# SQUID_Channel.net
KiCad netlist of a schematic drawn in Altium Designer
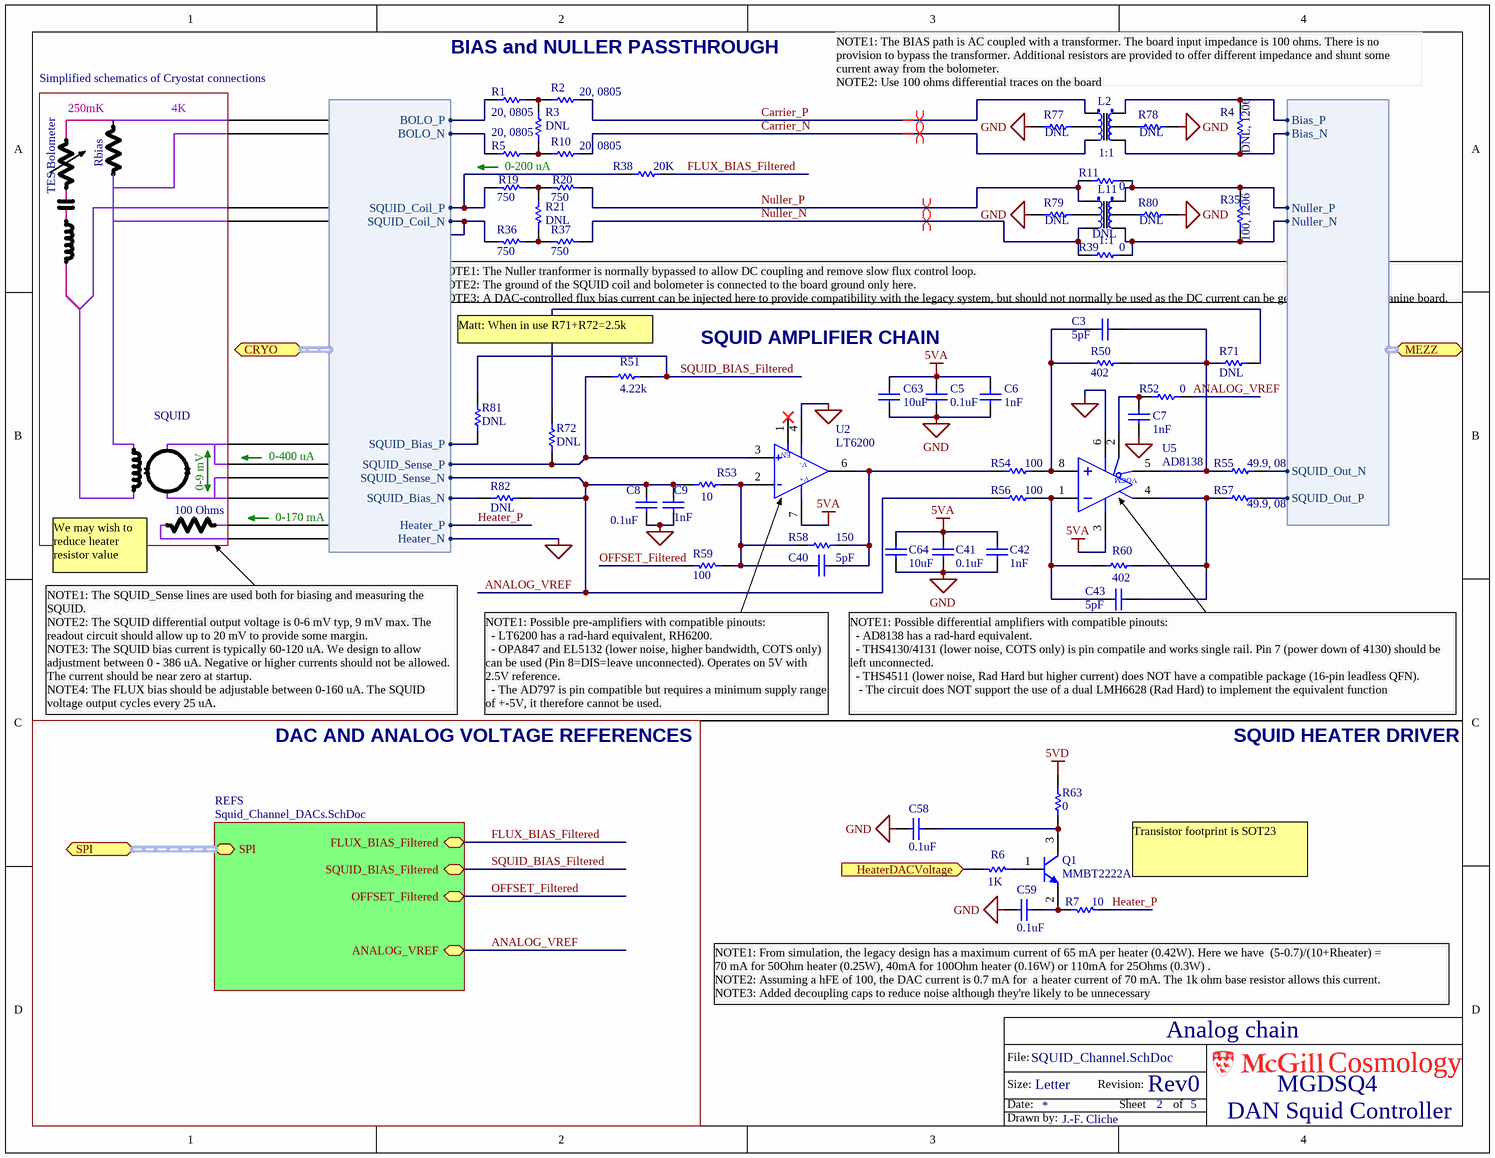
[diagram p0: SQUID_Channel.SchDoc]

(export (version "E")
  (design (tool "Eeschema 10.0.6"))
  (components
    (comp (ref "C3")
      (value "5pF")
      (footprint "0603")
      (description "Capacitor, Ceramic, 0603")
      (fields (field (name "MANUFACTURER") "Generic"))
      (libsource (lib "MiniSquidCtrl") (part "Cap0603"))
    )
    (comp (ref "C5")
      (value "0.1uF")
      (footprint "0603")
      (description "Capacitor, Ceramic, 0603")
      (fields (field (name "MANUFACTURER") "Generic"))
      (libsource (lib "MiniSquidCtrl") (part "Cap0603"))
    )
    (comp (ref "C6")
      (value "1nF")
      (footprint "0603")
      (description "Capacitor, Ceramic, 0603")
      (fields (field (name "MANUFACTURER") "Generic"))
      (libsource (lib "MiniSquidCtrl") (part "Cap0603"))
    )
    (comp (ref "C7")
      (value "1nF")
      (footprint "0603")
      (description "Capacitor, Ceramic, 0603")
      (fields (field (name "MANUFACTURER") "Generic"))
      (libsource (lib "MiniSquidCtrl") (part "Cap0603"))
    )
    (comp (ref "C8")
      (value "0.1uF")
      (footprint "0603")
      (description "Capacitor, Ceramic, 0603")
      (fields (field (name "MANUFACTURER") "Generic"))
      (libsource (lib "MiniSquidCtrl") (part "Cap0603"))
    )
    (comp (ref "C9")
      (value "1nF")
      (footprint "0603")
      (description "Capacitor, Ceramic, 0603")
      (fields (field (name "MANUFACTURER") "Generic"))
      (libsource (lib "MiniSquidCtrl") (part "Cap0603"))
    )
    (comp (ref "C40")
      (value "5pF")
      (footprint "0603")
      (description "Capacitor, Ceramic, 0603")
      (fields (field (name "MANUFACTURER") "Generic"))
      (libsource (lib "MiniSquidCtrl") (part "Cap0603"))
    )
    (comp (ref "C41")
      (value "0.1uF")
      (footprint "0603")
      (description "Capacitor, Ceramic, 0603")
      (fields (field (name "MANUFACTURER") "Generic"))
      (libsource (lib "MiniSquidCtrl") (part "Cap0603"))
    )
    (comp (ref "C42")
      (value "1nF")
      (footprint "0603")
      (description "Capacitor, Ceramic, 0603")
      (fields (field (name "MANUFACTURER") "Generic"))
      (libsource (lib "MiniSquidCtrl") (part "Cap0603"))
    )
    (comp (ref "C43")
      (value "5pF")
      (footprint "0603")
      (description "Capacitor, Ceramic, 0603")
      (fields (field (name "MANUFACTURER") "Generic"))
      (libsource (lib "MiniSquidCtrl") (part "Cap0603"))
    )
    (comp (ref "C58")
      (value "0.1uF")
      (footprint "0603")
      (description "Capacitor, Ceramic, 0603")
      (fields (field (name "MANUFACTURER") "Generic"))
      (libsource (lib "MiniSquidCtrl") (part "Cap0603"))
    )
    (comp (ref "C59")
      (value "0.1uF")
      (footprint "0603")
      (description "Capacitor, Ceramic, 0603")
      (fields (field (name "MANUFACTURER") "Generic"))
      (libsource (lib "MiniSquidCtrl") (part "Cap0603"))
    )
    (comp (ref "C63")
      (value "10uF")
      (footprint "CC3225-1210")
      (description "Capacitor, Ceramic, 1210")
      (fields (field (name "MANUFACTURER PART NUMBER") "1206YD106KAT2A") (field (name "VOLTAGE") "16V"))
      (libsource (lib "MiniSquidCtrl") (part "CAP 1210"))
    )
    (comp (ref "C64")
      (value "10uF")
      (footprint "CC3225-1210")
      (description "Capacitor, Ceramic, 1210")
      (fields (field (name "MANUFACTURER PART NUMBER") "1206YD106KAT2A") (field (name "VOLTAGE") "16V"))
      (libsource (lib "MiniSquidCtrl") (part "CAP 1210"))
    )
    (comp (ref "L2")
      (value "Transformer")
      (footprint "TTWB")
      (fields (field (name "MANUFACTURER") "Coilcraft"))
      (libsource (lib "MiniSquidCtrl") (part "Transformer"))
    )
    (comp (ref "L11")
      (value "DNL")
      (footprint "TTWB")
      (description "Transformer")
      (fields (field (name "MANUFACTURER") "Coilcraft"))
      (libsource (lib "MiniSquidCtrl") (part "Transformer"))
    )
    (comp (ref "Q1")
      (value "MMBT2222A")
      (footprint "SOT23")
      (description "TRANS NPN 40V 350MW SMD SOT23-3")
      (fields (field (name "MANUFACTURER") "Diodes Inc"))
      (libsource (lib "MiniSquidCtrl") (part "2N2222"))
    )
    (comp (ref "R1")
      (value "20, 0805")
      (footprint "0805")
      (description "RES 0805 SMD")
      (fields (field (name "MANUFACTURER") "Generic"))
      (libsource (lib "MiniSquidCtrl") (part "RES 0805"))
    )
    (comp (ref "R2")
      (value "20, 0805")
      (footprint "0805")
      (description "RES 0805 SMD")
      (fields (field (name "MANUFACTURER") "Generic"))
      (libsource (lib "MiniSquidCtrl") (part "RES 0805"))
    )
    (comp (ref "R3")
      (value "DNL")
      (footprint "0805")
      (description "RES 0805 SMD")
      (fields (field (name "MANUFACTURER") "Generic"))
      (libsource (lib "MiniSquidCtrl") (part "RES 0805"))
    )
    (comp (ref "R4")
      (value "DNL, 1206")
      (footprint "1206")
      (description "RES 100 OHM 1/4W 1206 SMD")
      (fields
        (field (name "MANUFACTURERS PART NUMBER") "DNL")
        (field (name "MANUFACTURER") "Rohm Semiconductor")
      )
      (libsource (lib "MiniSquidCtrl") (part "RES 1206"))
    )
    (comp (ref "R5")
      (value "20, 0805")
      (footprint "0805")
      (description "RES 0805 SMD")
      (fields (field (name "MANUFACTURER") "Generic"))
      (libsource (lib "MiniSquidCtrl") (part "RES 0805"))
    )
    (comp (ref "R6")
      (value "1K")
      (footprint "0603")
      (description "RES 0603")
      (fields (field (name "MANUFACTURER") "Generic") (field (name "Comment") "1k"))
      (libsource (lib "MiniSquidCtrl") (part "RES 0603"))
    )
    (comp (ref "R7")
      (value "10")
      (footprint "0603")
      (description "RES 0603")
      (fields (field (name "MANUFACTURER") "Generic"))
      (libsource (lib "MiniSquidCtrl") (part "RES 0603"))
    )
    (comp (ref "R10")
      (value "20, 0805")
      (footprint "0805")
      (description "RES 0805 SMD")
      (fields (field (name "MANUFACTURER") "Generic"))
      (libsource (lib "MiniSquidCtrl") (part "RES 0805"))
    )
    (comp (ref "R11")
      (value "0")
      (footprint "0603")
      (description "RES 0603")
      (fields (field (name "MANUFACTURER") "Generic"))
      (libsource (lib "MiniSquidCtrl") (part "Res0603"))
    )
    (comp (ref "R19")
      (value "750")
      (footprint "0603")
      (description "RES 0603")
      (fields (field (name "MANUFACTURER") "Generic"))
      (libsource (lib "MiniSquidCtrl") (part "Res0603"))
    )
    (comp (ref "R20")
      (value "750")
      (footprint "0603")
      (description "RES 0603")
      (fields (field (name "MANUFACTURER") "Generic"))
      (libsource (lib "MiniSquidCtrl") (part "Res0603"))
    )
    (comp (ref "R21")
      (value "DNL")
      (footprint "0603")
      (description "RES 0603")
      (fields (field (name "MANUFACTURER") "Generic"))
      (libsource (lib "MiniSquidCtrl") (part "Res0603"))
    )
    (comp (ref "R35")
      (value "100, 1206")
      (footprint "1206")
      (description "RES 100 OHM 1/4W 1206 SMD")
      (fields
        (field (name "MANUFACTURERS PART NUMBER") "ESR18EZPF1000")
        (field (name "MANUFACTURER") "Rohm Semiconductor")
      )
      (libsource (lib "MiniSquidCtrl") (part "RES 1206"))
    )
    (comp (ref "R36")
      (value "750")
      (footprint "0603")
      (description "RES 0603")
      (fields (field (name "MANUFACTURER") "Generic"))
      (libsource (lib "MiniSquidCtrl") (part "Res0603"))
    )
    (comp (ref "R37")
      (value "750")
      (footprint "0603")
      (description "RES 0603")
      (fields (field (name "MANUFACTURER") "Generic"))
      (libsource (lib "MiniSquidCtrl") (part "Res0603"))
    )
    (comp (ref "R38")
      (value "20K")
      (footprint "0603")
      (description "RES 0603")
      (fields (field (name "MANUFACTURER") "Generic") (field (name "Comment") "20k"))
      (libsource (lib "MiniSquidCtrl") (part "Res0603"))
    )
    (comp (ref "R39")
      (value "0")
      (footprint "0603")
      (description "RES 0603")
      (fields (field (name "MANUFACTURER") "Generic"))
      (libsource (lib "MiniSquidCtrl") (part "Res0603"))
    )
    (comp (ref "R48")
      (value "0")
      (footprint "0603")
      (description "RES 0603")
      (fields (field (name "MANUFACTURER") "Generic"))
      (libsource (lib "MiniSquidCtrl") (part "Res0603"))
    )
    (comp (ref "R50")
      (value "402")
      (footprint "0603")
      (description "RES 0603")
      (fields (field (name "MANUFACTURER") "Generic"))
      (libsource (lib "MiniSquidCtrl") (part "RES 0603"))
    )
    (comp (ref "R51")
      (value "4.22k")
      (footprint "0603")
      (description "RES 0603")
      (fields (field (name "MANUFACTURER") "Generic"))
      (libsource (lib "MiniSquidCtrl") (part "Res0603"))
    )
    (comp (ref "R52")
      (value "0")
      (footprint "0603")
      (description "RES 0603")
      (fields (field (name "MANUFACTURER") "Generic"))
      (libsource (lib "MiniSquidCtrl") (part "Res0603"))
    )
    (comp (ref "R53")
      (value "10")
      (footprint "0603")
      (description "RES 0603")
      (fields (field (name "MANUFACTURER") "Generic"))
      (libsource (lib "MiniSquidCtrl") (part "Res0603"))
    )
    (comp (ref "R54")
      (value "100")
      (footprint "0603")
      (description "RES 0603")
      (fields (field (name "MANUFACTURER") "Generic"))
      (libsource (lib "MiniSquidCtrl") (part "Res0603"))
    )
    (comp (ref "R55")
      (value "49.9, 0805")
      (footprint "0805")
      (description "RES 0805 SMD")
      (fields (field (name "MANUFACTURER") "Generic"))
      (libsource (lib "MiniSquidCtrl") (part "RES 0805"))
    )
    (comp (ref "R56")
      (value "100")
      (footprint "0603")
      (description "RES 0603")
      (fields (field (name "MANUFACTURER") "Generic"))
      (libsource (lib "MiniSquidCtrl") (part "Res0603"))
    )
    (comp (ref "R57")
      (value "49.9, 0805")
      (footprint "0805")
      (description "RES 0805 SMD")
      (fields (field (name "MANUFACTURER") "Generic"))
      (libsource (lib "MiniSquidCtrl") (part "RES 0805"))
    )
    (comp (ref "R58")
      (value "150")
      (footprint "0603")
      (description "RES 0603")
      (fields (field (name "MANUFACTURER") "Generic"))
      (libsource (lib "MiniSquidCtrl") (part "Res0603"))
    )
    (comp (ref "R59")
      (value "100")
      (footprint "0603")
      (description "RES 0603")
      (fields (field (name "MANUFACTURER") "Generic"))
      (libsource (lib "MiniSquidCtrl") (part "Res0603"))
    )
    (comp (ref "R60")
      (value "402")
      (footprint "0603")
      (description "RES 0603")
      (fields (field (name "MANUFACTURER") "Generic"))
      (libsource (lib "MiniSquidCtrl") (part "Res0603"))
    )
    (comp (ref "R63")
      (value "0")
      (footprint "0603")
      (description "RES 0603")
      (fields (field (name "MANUFACTURER") "Generic"))
      (libsource (lib "MiniSquidCtrl") (part "Res0603"))
    )
    (comp (ref "R71")
      (value "DNL")
      (footprint "0603")
      (description "RES 0603")
      (fields (field (name "MANUFACTURER") "Generic"))
      (libsource (lib "MiniSquidCtrl") (part "Res0603"))
    )
    (comp (ref "R72")
      (value "DNL")
      (footprint "0603")
      (description "RES 0603")
      (fields (field (name "MANUFACTURER") "Generic"))
      (libsource (lib "MiniSquidCtrl") (part "Res0603"))
    )
    (comp (ref "R77")
      (value "DNL")
      (footprint "0603")
      (description "RES 0603")
      (fields (field (name "MANUFACTURER") "Generic"))
      (libsource (lib "MiniSquidCtrl") (part "Res0603"))
    )
    (comp (ref "R78")
      (value "DNL")
      (footprint "0603")
      (description "RES 0603")
      (fields (field (name "MANUFACTURER") "Generic"))
      (libsource (lib "MiniSquidCtrl") (part "Res0603"))
    )
    (comp (ref "R79")
      (value "DNL")
      (footprint "0603")
      (description "RES 0603")
      (fields (field (name "MANUFACTURER") "Generic"))
      (libsource (lib "MiniSquidCtrl") (part "Res0603"))
    )
    (comp (ref "R80")
      (value "DNL")
      (footprint "0603")
      (description "RES 0603")
      (fields (field (name "MANUFACTURER") "Generic"))
      (libsource (lib "MiniSquidCtrl") (part "Res0603"))
    )
    (comp (ref "R81")
      (value "DNL")
      (footprint "0603")
      (description "RES 0603")
      (fields (field (name "MANUFACTURER") "Generic"))
      (libsource (lib "MiniSquidCtrl") (part "Res0603"))
    )
    (comp (ref "R82")
      (value "DNL")
      (footprint "0603")
      (description "RES 0603")
      (fields (field (name "MANUFACTURER") "Generic"))
      (libsource (lib "MiniSquidCtrl") (part "Res0603"))
    )
    (comp (ref "U2")
      (value "LT6200")
      (footprint "SO8")
      (description "IC OPAMP R-R I/O 165MHZ 8-SOIC")
      (fields (field (name "MANUFACTURER") "Linear Technology"))
      (libsource (lib "MiniSquidCtrl") (part "LT6200"))
    )
    (comp (ref "U5")
      (value "AD8138")
      (footprint "SO8")
      (description "IC AMP DIFF LDIST LP 95MA 8SOIC")
      (fields (field (name "MANUFACTURER") "Analog Devices Inc"))
      (libsource (lib "MiniSquidCtrl") (part "AD8138"))
    )
  )
  (nets
    (net (code "4") (name "/ANALOG_VREF") (class "Default")
      (node (ref "C8") (pin "2") (pinfunction "2_2") (pintype "passive"))
      (node (ref "C9") (pin "2") (pinfunction "2_2") (pintype "passive"))
      (node (ref "R52") (pin "1") (pinfunction "1_1") (pintype "passive"))
      (node (ref "R53") (pin "2") (pinfunction "2_2") (pintype "passive"))
      (node (ref "R56") (pin "2") (pinfunction "2_2") (pintype "passive"))
      (node (ref "R82") (pin "2") (pinfunction "2_2") (pintype "passive"))
    )
    (net (code "5") (name "/BOLO_N") (class "Default")
      (node (ref "R5") (pin "1") (pinfunction "1_1") (pintype "passive"))
    )
    (net (code "6") (name "/BOLO_P") (class "Default")
      (node (ref "R1") (pin "1") (pinfunction "1_1") (pintype "passive"))
    )
    (net (code "7") (name "/Bias_N") (class "Default")
      (node (ref "L2") (pin "4") (pinfunction "Sec_4") (pintype "passive"))
      (node (ref "R4") (pin "2") (pinfunction "2_2") (pintype "passive"))
    )
    (net (code "8") (name "/Bias_P") (class "Default")
      (node (ref "L2") (pin "6") (pinfunction "SecDot_6") (pintype "passive"))
      (node (ref "R4") (pin "1") (pinfunction "1_1") (pintype "passive"))
    )
    (net (code "9") (name "/Carrier_N") (class "Default")
      (node (ref "L2") (pin "3") (pinfunction "Prim_3") (pintype "passive"))
      (node (ref "R10") (pin "1") (pinfunction "1_1") (pintype "passive"))
    )
    (net (code "10") (name "/Carrier_P") (class "Default")
      (node (ref "L2") (pin "1") (pinfunction "PrimDot_1") (pintype "passive"))
      (node (ref "R2") (pin "1") (pinfunction "1_1") (pintype "passive"))
    )
    (net (code "11") (name "/FLUX_BIAS_Filtered") (class "Default")
      (node (ref "R38") (pin "1") (pinfunction "1_1") (pintype "passive"))
    )
    (net (code "12") (name "/HeaterDACVoltage") (class "Default")
      (node (ref "R6") (pin "2") (pinfunction "2_2") (pintype "passive"))
    )
    (net (code "13") (name "/Heater_P") (class "Default")
      (node (ref "R7") (pin "1") (pinfunction "1_1") (pintype "passive"))
    )
    (net (code "14") (name "/Nuller_N") (class "Default")
      (node (ref "L11") (pin "3") (pinfunction "Prim_3") (pintype "passive"))
      (node (ref "R37") (pin "2") (pinfunction "2_2") (pintype "passive"))
      (node (ref "R39") (pin "2") (pinfunction "2_2") (pintype "passive"))
    )
    (net (code "15") (name "/Nuller_P") (class "Default")
      (node (ref "L11") (pin "1") (pinfunction "PrimDot_1") (pintype "passive"))
      (node (ref "R11") (pin "2") (pinfunction "2_2") (pintype "passive"))
      (node (ref "R20") (pin "2") (pinfunction "2_2") (pintype "passive"))
    )
    (net (code "16") (name "/OFFSET_Filtered") (class "Default")
      (node (ref "R59") (pin "1") (pinfunction "1_1") (pintype "passive"))
    )
    (net (code "18") (name "/SQUID_BIAS_Filtered") (class "Default")
      (node (ref "R51") (pin "1") (pinfunction "1_1") (pintype "passive"))
      (node (ref "R81") (pin "1") (pinfunction "1_1") (pintype "passive"))
    )
    (net (code "19") (name "/SQUID_Bias_N") (class "Default")
      (node (ref "R82") (pin "1") (pinfunction "1_1") (pintype "passive"))
    )
    (net (code "20") (name "/SQUID_Bias_P") (class "Default")
      (node (ref "R81") (pin "2") (pinfunction "2_2") (pintype "passive"))
    )
    (net (code "21") (name "/SQUID_Coil_N") (class "Default")
      (node (ref "R36") (pin "2") (pinfunction "2_2") (pintype "passive"))
      (node (ref "R48") (pin "1") (pinfunction "1_1") (pintype "passive"))
    )
    (net (code "22") (name "/SQUID_Coil_P") (class "Default")
      (node (ref "R19") (pin "2") (pinfunction "2_2") (pintype "passive"))
      (node (ref "R38") (pin "2") (pinfunction "2_2") (pintype "passive"))
    )
    (net (code "23") (name "/SQUID_Out_N") (class "Default")
      (node (ref "R55") (pin "2") (pinfunction "2_2") (pintype "passive"))
    )
    (net (code "24") (name "/SQUID_Out_P") (class "Default")
      (node (ref "R57") (pin "2") (pinfunction "2_2") (pintype "passive"))
    )
    (net (code "25") (name "/SQUID_Sense_P") (class "Default")
      (node (ref "R51") (pin "2") (pinfunction "2_2") (pintype "passive"))
      (node (ref "R72") (pin "2") (pinfunction "2_2") (pintype "passive"))
      (node (ref "U2") (pin "3") (pinfunction "IN+_3") (pintype "passive"))
    )
    (net (code "28") (name "5VA") (class "Default")
      (node (ref "C41") (pin "2") (pinfunction "2_2") (pintype "passive"))
      (node (ref "C42") (pin "2") (pinfunction "2_2") (pintype "passive"))
      (node (ref "C5") (pin "2") (pinfunction "2_2") (pintype "passive"))
      (node (ref "C6") (pin "2") (pinfunction "2_2") (pintype "passive"))
      (node (ref "C63") (pin "2") (pinfunction "2_2") (pintype "passive"))
      (node (ref "C64") (pin "2") (pinfunction "2_2") (pintype "passive"))
      (node (ref "U2") (pin "7") (pinfunction "V+_7") (pintype "power_in"))
      (node (ref "U5") (pin "3") (pinfunction "V+_3") (pintype "power_in"))
    )
    (net (code "29") (name "5VD") (class "Default")
      (node (ref "R63") (pin "1") (pinfunction "1_1") (pintype "passive"))
    )
    (net (code "30") (name "GND") (class "Default")
      (node (ref "C41") (pin "1") (pinfunction "1_1") (pintype "passive"))
      (node (ref "C42") (pin "1") (pinfunction "1_1") (pintype "passive"))
      (node (ref "C5") (pin "1") (pinfunction "1_1") (pintype "passive"))
      (node (ref "C58") (pin "2") (pinfunction "2_2") (pintype "passive"))
      (node (ref "C59") (pin "2") (pinfunction "2_2") (pintype "passive"))
      (node (ref "C6") (pin "1") (pinfunction "1_1") (pintype "passive"))
      (node (ref "C63") (pin "1") (pinfunction "1_1") (pintype "passive"))
      (node (ref "C64") (pin "1") (pinfunction "1_1") (pintype "passive"))
      (node (ref "C7") (pin "1") (pinfunction "1_1") (pintype "passive"))
      (node (ref "C8") (pin "1") (pinfunction "1_1") (pintype "passive"))
      (node (ref "C9") (pin "1") (pinfunction "1_1") (pintype "passive"))
      (node (ref "R48") (pin "2") (pinfunction "2_2") (pintype "passive"))
      (node (ref "R77") (pin "1") (pinfunction "1_1") (pintype "passive"))
      (node (ref "R78") (pin "2") (pinfunction "2_2") (pintype "passive"))
      (node (ref "R79") (pin "1") (pinfunction "1_1") (pintype "passive"))
      (node (ref "R80") (pin "2") (pinfunction "2_2") (pintype "passive"))
      (node (ref "U2") (pin "4") (pinfunction "V-_4") (pintype "power_in"))
      (node (ref "U5") (pin "6") (pinfunction "V-_6") (pintype "power_in"))
    )
    (net (code "31") (name "Net-(L2-PrimCent)") (class "Default")
      (node (ref "L2") (pin "2") (pinfunction "PrimCent_2") (pintype "passive"))
      (node (ref "R77") (pin "2") (pinfunction "2_2") (pintype "passive"))
    )
    (net (code "32") (name "Net-(L2-SecCent)") (class "Default")
      (node (ref "L2") (pin "5") (pinfunction "SecCent_5") (pintype "passive"))
      (node (ref "R78") (pin "1") (pinfunction "1_1") (pintype "passive"))
    )
    (net (code "33") (name "Net-(L11-PrimCent)") (class "Default")
      (node (ref "L11") (pin "2") (pinfunction "PrimCent_2") (pintype "passive"))
      (node (ref "R79") (pin "2") (pinfunction "2_2") (pintype "passive"))
    )
    (net (code "34") (name "Net-(L11-Sec)") (class "Default")
      (node (ref "L11") (pin "4") (pinfunction "Sec_4") (pintype "passive"))
      (node (ref "R35") (pin "2") (pinfunction "2_2") (pintype "passive"))
      (node (ref "R39") (pin "1") (pinfunction "1_1") (pintype "passive"))
    )
    (net (code "35") (name "Net-(L11-SecCent)") (class "Default")
      (node (ref "L11") (pin "5") (pinfunction "SecCent_5") (pintype "passive"))
      (node (ref "R80") (pin "1") (pinfunction "1_1") (pintype "passive"))
    )
    (net (code "36") (name "Net-(L11-SecDot)") (class "Default")
      (node (ref "L11") (pin "6") (pinfunction "SecDot_6") (pintype "passive"))
      (node (ref "R11") (pin "1") (pinfunction "1_1") (pintype "passive"))
      (node (ref "R35") (pin "1") (pinfunction "1_1") (pintype "passive"))
    )
    (net (code "37") (name "Net-(Q1-B)") (class "Default")
      (node (ref "Q1") (pin "1") (pinfunction "B_1") (pintype "passive"))
      (node (ref "R6") (pin "1") (pinfunction "1_1") (pintype "passive"))
    )
    (net (code "38") (name "Net-(Q1-C)") (class "Default")
      (node (ref "C58") (pin "1") (pinfunction "1_1") (pintype "passive"))
      (node (ref "Q1") (pin "3") (pinfunction "C_3") (pintype "passive"))
      (node (ref "R63") (pin "2") (pinfunction "2_2") (pintype "passive"))
    )
    (net (code "39") (name "Net-(Q1-E)") (class "Default")
      (node (ref "C59") (pin "1") (pinfunction "1_1") (pintype "passive"))
      (node (ref "Q1") (pin "2") (pinfunction "E_2") (pintype "passive"))
      (node (ref "R7") (pin "2") (pinfunction "2_2") (pintype "passive"))
    )
    (net (code "40") (name "Net-(R1-Pad2)") (class "Default")
      (node (ref "R1") (pin "2") (pinfunction "2_2") (pintype "passive"))
      (node (ref "R2") (pin "2") (pinfunction "2_2") (pintype "passive"))
      (node (ref "R3") (pin "1") (pinfunction "1_1") (pintype "passive"))
    )
    (net (code "41") (name "Net-(R10-Pad2)") (class "Default")
      (node (ref "R10") (pin "2") (pinfunction "2_2") (pintype "passive"))
      (node (ref "R3") (pin "2") (pinfunction "2_2") (pintype "passive"))
      (node (ref "R5") (pin "2") (pinfunction "2_2") (pintype "passive"))
    )
    (net (code "42") (name "Net-(R19-Pad1)") (class "Default")
      (node (ref "R19") (pin "1") (pinfunction "1_1") (pintype "passive"))
      (node (ref "R20") (pin "1") (pinfunction "1_1") (pintype "passive"))
      (node (ref "R21") (pin "1") (pinfunction "1_1") (pintype "passive"))
    )
    (net (code "43") (name "Net-(R21-Pad2)") (class "Default")
      (node (ref "R21") (pin "2") (pinfunction "2_2") (pintype "passive"))
      (node (ref "R36") (pin "1") (pinfunction "1_1") (pintype "passive"))
      (node (ref "R37") (pin "1") (pinfunction "1_1") (pintype "passive"))
    )
    (net (code "44") (name "Net-(R71-Pad2)") (class "Default")
      (node (ref "R71") (pin "2") (pinfunction "2_2") (pintype "passive"))
      (node (ref "R72") (pin "1") (pinfunction "1_1") (pintype "passive"))
    )
    (net (code "45") (name "Net-(U2-IN-)") (class "Default")
      (node (ref "C40") (pin "2") (pinfunction "2_2") (pintype "passive"))
      (node (ref "R53") (pin "1") (pinfunction "1_1") (pintype "passive"))
      (node (ref "R58") (pin "2") (pinfunction "2_2") (pintype "passive"))
      (node (ref "R59") (pin "2") (pinfunction "2_2") (pintype "passive"))
      (node (ref "U2") (pin "2") (pinfunction "IN-_2") (pintype "passive"))
    )
    (net (code "46") (name "Net-(U2-OUT-)") (class "Default")
      (node (ref "C40") (pin "1") (pinfunction "1_1") (pintype "passive"))
      (node (ref "R54") (pin "2") (pinfunction "2_2") (pintype "passive"))
      (node (ref "R58") (pin "1") (pinfunction "1_1") (pintype "passive"))
      (node (ref "U2") (pin "6") (pinfunction "OUT-_6") (pintype "passive"))
    )
    (net (code "47") (name "Net-(U5-IN+)") (class "Default")
      (node (ref "C3") (pin "2") (pinfunction "2_2") (pintype "passive"))
      (node (ref "R50") (pin "2") (pinfunction "2_2") (pintype "passive"))
      (node (ref "R54") (pin "1") (pinfunction "1_1") (pintype "passive"))
      (node (ref "U5") (pin "8") (pinfunction "IN+_8") (pintype "passive"))
    )
    (net (code "48") (name "Net-(U5-IN-)") (class "Default")
      (node (ref "C43") (pin "2") (pinfunction "2_2") (pintype "passive"))
      (node (ref "R56") (pin "1") (pinfunction "1_1") (pintype "passive"))
      (node (ref "R60") (pin "2") (pinfunction "2_2") (pintype "passive"))
      (node (ref "U5") (pin "1") (pinfunction "IN-_1") (pintype "passive"))
    )
    (net (code "49") (name "Net-(U5-OUT+)") (class "Default")
      (node (ref "C43") (pin "1") (pinfunction "1_1") (pintype "passive"))
      (node (ref "R57") (pin "1") (pinfunction "1_1") (pintype "passive"))
      (node (ref "R60") (pin "1") (pinfunction "1_1") (pintype "passive"))
      (node (ref "U5") (pin "4") (pinfunction "OUT+_4") (pintype "passive"))
    )
    (net (code "50") (name "Net-(U5-OUT-)") (class "Default")
      (node (ref "C3") (pin "1") (pinfunction "1_1") (pintype "passive"))
      (node (ref "R50") (pin "1") (pinfunction "1_1") (pintype "passive"))
      (node (ref "R55") (pin "1") (pinfunction "1_1") (pintype "passive"))
      (node (ref "R71") (pin "1") (pinfunction "1_1") (pintype "passive"))
      (node (ref "U5") (pin "5") (pinfunction "OUT-_5") (pintype "passive"))
    )
    (net (code "51") (name "Net-(U5-VOCM)") (class "Default")
      (node (ref "C7") (pin "2") (pinfunction "2_2") (pintype "passive"))
      (node (ref "R52") (pin "2") (pinfunction "2_2") (pintype "passive"))
      (node (ref "U5") (pin "2") (pinfunction "VOCM_2") (pintype "passive"))
    )
    (net (code "52") (name "unconnected-(U2-SHDN-Pad1)") (class "Default")
      (node (ref "U2") (pin "1") (pinfunction "SHDN_1") (pintype "passive+no_connect"))
    )
    (net (code "53") (name "unconnected-(U5-NC-Pad7)") (class "Default")
      (node (ref "U5") (pin "7") (pinfunction "NC_7") (pintype "passive"))
    )
  )
)
